# Connectors.net
KiCad netlist of a schematic drawn in Altium Designer
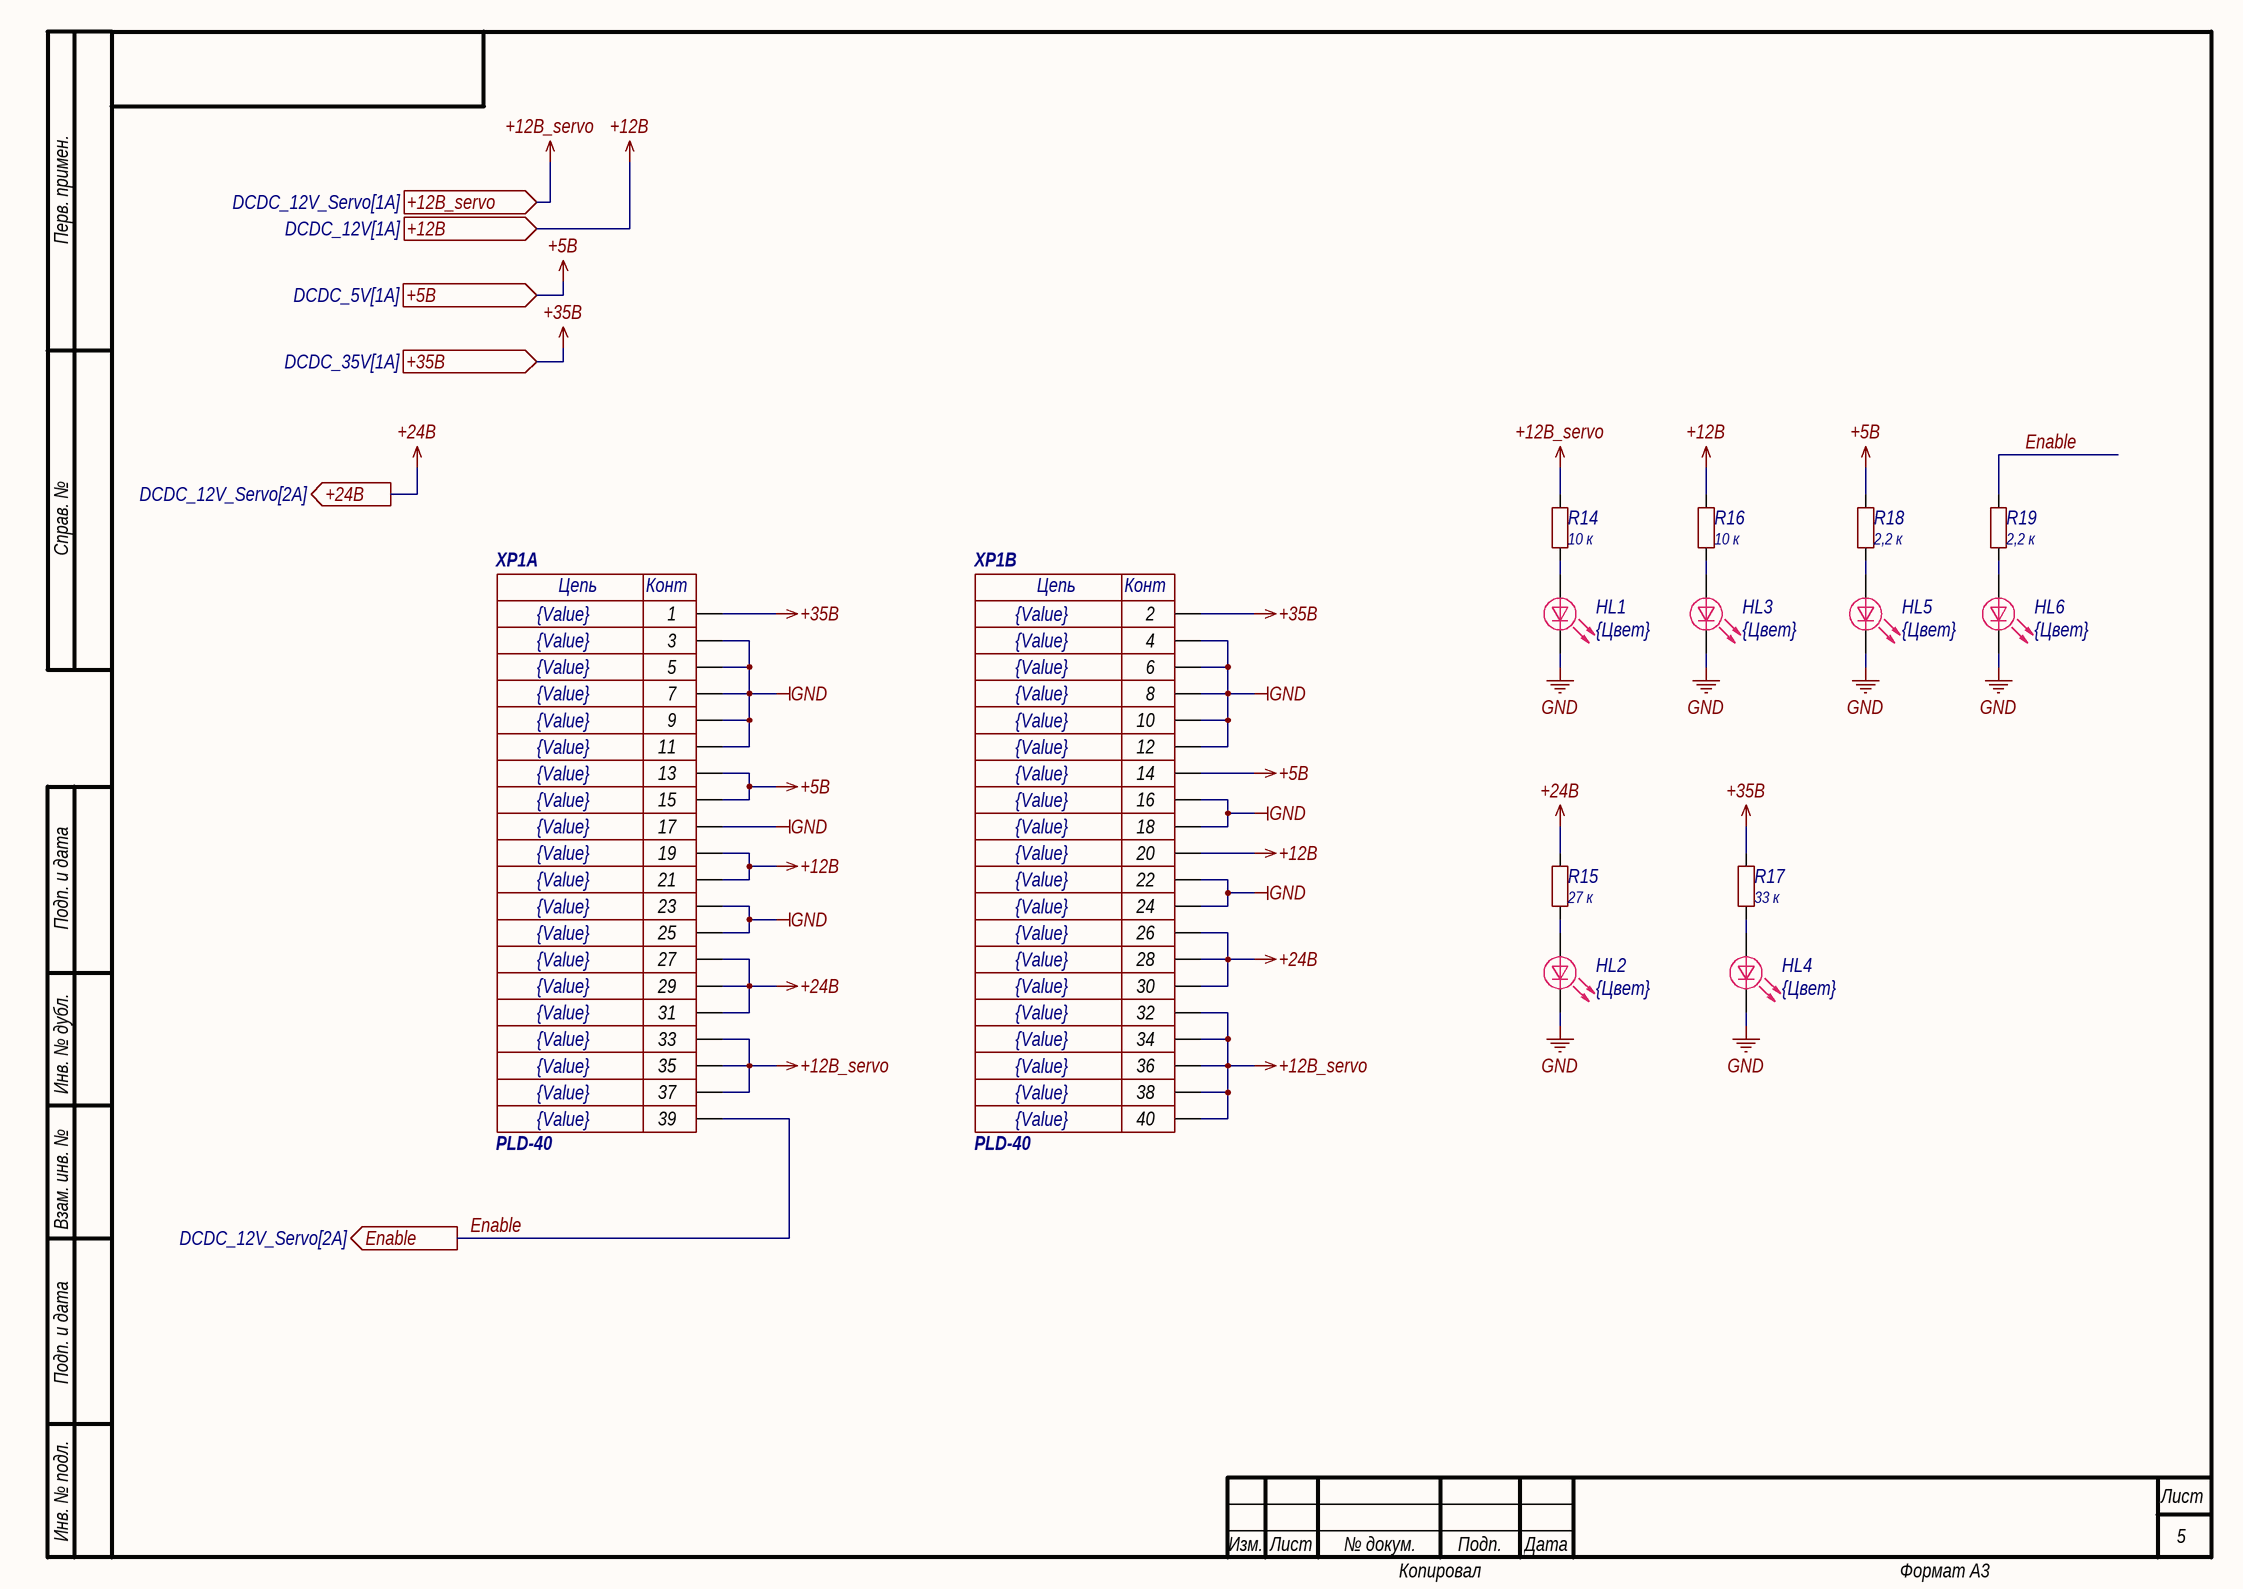
[diagram p0: Connectors.SchDoc]

(export (version "E")
  (design (tool "Eeschema 10.0.6"))
  (components
    (comp (ref "HL1")
      (value "LED")
      (footprint "0805D")
      (description "Светодиод")
      (fields (field (name "COLOR") "{Цвет}"))
      (libsource (lib "Hydrolib") (part "LED"))
    )
    (comp (ref "HL2")
      (value "LED")
      (footprint "0805D")
      (description "Светодиод")
      (fields (field (name "COLOR") "{Цвет}"))
      (libsource (lib "Hydrolib") (part "LED"))
    )
    (comp (ref "HL3")
      (value "LED")
      (footprint "0805D")
      (description "Светодиод")
      (fields (field (name "COLOR") "{Цвет}"))
      (libsource (lib "Hydrolib") (part "LED"))
    )
    (comp (ref "HL4")
      (value "LED")
      (footprint "0805D")
      (description "Светодиод")
      (fields (field (name "COLOR") "{Цвет}"))
      (libsource (lib "Hydrolib") (part "LED"))
    )
    (comp (ref "HL5")
      (value "LED")
      (footprint "0805D")
      (description "Светодиод")
      (fields (field (name "COLOR") "{Цвет}"))
      (libsource (lib "Hydrolib") (part "LED"))
    )
    (comp (ref "HL6")
      (value "LED")
      (footprint "0805D")
      (description "Светодиод")
      (fields (field (name "COLOR") "{Цвет}"))
      (libsource (lib "Hydrolib") (part "LED"))
    )
    (comp (ref "R14")
      (value "10 к")
      (footprint "0603R")
      (description "Резистор номиналом 10 кОм и точностью 1%")
      (fields (field (name "PART NUMBER") "Resistor_10k_1_0603") (field (name "TOLERANCE") "1%"))
      (libsource (lib "Hydrolib") (part "Resistor"))
    )
    (comp (ref "R15")
      (value "27 к")
      (footprint "0603R")
      (description "Резистор номиналом 27 кОм и точностью 1%")
      (fields (field (name "PART NUMBER") "Resistor_27k_1_0603") (field (name "TOLERANCE") "1%"))
      (libsource (lib "Hydrolib") (part "Resistor"))
    )
    (comp (ref "R16")
      (value "10 к")
      (footprint "0603R")
      (description "Резистор номиналом 10 кОм и точностью 1%")
      (fields (field (name "PART NUMBER") "Resistor_10k_1_0603") (field (name "TOLERANCE") "1%"))
      (libsource (lib "Hydrolib") (part "Resistor"))
    )
    (comp (ref "R17")
      (value "33 к")
      (footprint "0603R")
      (description "Резистор номиналом 33 кОм и точностью 1%")
      (fields (field (name "PART NUMBER") "Resistor_33k_1_0603") (field (name "TOLERANCE") "1%"))
      (libsource (lib "Hydrolib") (part "Resistor"))
    )
    (comp (ref "R18")
      (value "2,2 к")
      (footprint "0603R")
      (description "Резистор номиналом 2,2 кОм и точностью 1%")
      (fields (field (name "PART NUMBER") "Resistor_2.2k_1_0603") (field (name "TOLERANCE") "1%"))
      (libsource (lib "Hydrolib") (part "Resistor"))
    )
    (comp (ref "R19")
      (value "2,2 к")
      (footprint "0603R")
      (description "Резистор номиналом 2,2 кОм и точностью 1%")
      (fields (field (name "PART NUMBER") "Resistor_2.2k_1_0603") (field (name "TOLERANCE") "1%"))
      (libsource (lib "Hydrolib") (part "Resistor"))
    )
    (comp (ref "XP1")
      (value "PLD-40")
      (footprint "PLD40")
      (description "Гребенка 40 пинов")
      (fields
        (field (name "VALUE17") "{Value}")
        (field (name "VALUE20") "{Value}")
        (field (name "VALUE19") "{Value}")
        (field (name "VALUE18") "{Value}")
        (field (name "VALUE16") "{Value}")
        (field (name "VALUE15") "{Value}")
        (field (name "VALUE14") "{Value}")
        (field (name "VALUE13") "{Value}")
        (field (name "VALUE12") "{Value}")
        (field (name "VALUE11") "{Value}")
        (field (name "VALUE10") "{Value}")
        (field (name "VALUE9") "{Value}")
        (field (name "VALUE8") "{Value}")
        (field (name "VALUE7") "{Value}")
        (field (name "VALUE6") "{Value}")
        (field (name "VALUE5") "{Value}")
        (field (name "VALUE4") "{Value}")
        (field (name "VALUE3") "{Value}")
        (field (name "VALUE2") "{Value}")
        (field (name "VALUE1") "{Value}")
      )
      (libsource (lib "Hydrolib") (part "Conn_40pin_double"))
    )
  )
  (nets
    (net (code "1") (name "+5В") (class "Default")
      (node (ref "R18") (pin "2") (pinfunction "2_2") (pintype "passive"))
      (node (ref "XP1") (pin "13") (pinfunction "13_13") (pintype "passive"))
      (node (ref "XP1") (pin "14") (pinfunction "14_14") (pintype "passive"))
      (node (ref "XP1") (pin "15") (pinfunction "15_15") (pintype "passive"))
    )
    (net (code "2") (name "+12В") (class "Default")
      (node (ref "R16") (pin "2") (pinfunction "2_2") (pintype "passive"))
      (node (ref "XP1") (pin "19") (pinfunction "19_19") (pintype "passive"))
      (node (ref "XP1") (pin "20") (pinfunction "20_20") (pintype "passive"))
      (node (ref "XP1") (pin "21") (pinfunction "21_21") (pintype "passive"))
    )
    (net (code "3") (name "+12В_servo") (class "Default")
      (node (ref "R14") (pin "2") (pinfunction "2_2") (pintype "passive"))
      (node (ref "XP1") (pin "32") (pinfunction "32_32") (pintype "passive"))
      (node (ref "XP1") (pin "33") (pinfunction "33_33") (pintype "passive"))
      (node (ref "XP1") (pin "34") (pinfunction "34_34") (pintype "passive"))
      (node (ref "XP1") (pin "35") (pinfunction "35_35") (pintype "passive"))
      (node (ref "XP1") (pin "36") (pinfunction "36_36") (pintype "passive"))
      (node (ref "XP1") (pin "37") (pinfunction "37_37") (pintype "passive"))
      (node (ref "XP1") (pin "38") (pinfunction "38_38") (pintype "passive"))
      (node (ref "XP1") (pin "40") (pinfunction "40_40") (pintype "passive"))
    )
    (net (code "4") (name "+24В") (class "Default")
      (node (ref "R15") (pin "2") (pinfunction "2_2") (pintype "passive"))
      (node (ref "XP1") (pin "26") (pinfunction "26_26") (pintype "passive"))
      (node (ref "XP1") (pin "27") (pinfunction "27_27") (pintype "passive"))
      (node (ref "XP1") (pin "28") (pinfunction "28_28") (pintype "passive"))
      (node (ref "XP1") (pin "29") (pinfunction "29_29") (pintype "passive"))
      (node (ref "XP1") (pin "30") (pinfunction "30_30") (pintype "passive"))
      (node (ref "XP1") (pin "31") (pinfunction "31_31") (pintype "passive"))
    )
    (net (code "5") (name "+35В") (class "Default")
      (node (ref "R17") (pin "2") (pinfunction "2_2") (pintype "passive"))
      (node (ref "XP1") (pin "1") (pinfunction "1_1") (pintype "passive"))
      (node (ref "XP1") (pin "2") (pinfunction "2_2") (pintype "passive"))
    )
    (net (code "6") (name "/Enable") (class "Default")
      (node (ref "R19") (pin "2") (pinfunction "2_2") (pintype "passive"))
      (node (ref "XP1") (pin "39") (pinfunction "39_39") (pintype "passive"))
    )
    (net (code "7") (name "GND") (class "Default")
      (node (ref "HL1") (pin "2") (pinfunction "2_2") (pintype "passive"))
      (node (ref "HL2") (pin "2") (pinfunction "2_2") (pintype "passive"))
      (node (ref "HL3") (pin "2") (pinfunction "2_2") (pintype "passive"))
      (node (ref "HL4") (pin "2") (pinfunction "2_2") (pintype "passive"))
      (node (ref "HL5") (pin "2") (pinfunction "2_2") (pintype "passive"))
      (node (ref "HL6") (pin "2") (pinfunction "2_2") (pintype "passive"))
      (node (ref "XP1") (pin "10") (pinfunction "10_10") (pintype "passive"))
      (node (ref "XP1") (pin "11") (pinfunction "11_11") (pintype "passive"))
      (node (ref "XP1") (pin "12") (pinfunction "12_12") (pintype "passive"))
      (node (ref "XP1") (pin "16") (pinfunction "16_16") (pintype "passive"))
      (node (ref "XP1") (pin "17") (pinfunction "17_17") (pintype "passive"))
      (node (ref "XP1") (pin "18") (pinfunction "18_18") (pintype "passive"))
      (node (ref "XP1") (pin "22") (pinfunction "22_22") (pintype "passive"))
      (node (ref "XP1") (pin "23") (pinfunction "23_23") (pintype "passive"))
      (node (ref "XP1") (pin "24") (pinfunction "24_24") (pintype "passive"))
      (node (ref "XP1") (pin "25") (pinfunction "25_25") (pintype "passive"))
      (node (ref "XP1") (pin "3") (pinfunction "3_3") (pintype "passive"))
      (node (ref "XP1") (pin "4") (pinfunction "4_4") (pintype "passive"))
      (node (ref "XP1") (pin "5") (pinfunction "5_5") (pintype "passive"))
      (node (ref "XP1") (pin "6") (pinfunction "6_6") (pintype "passive"))
      (node (ref "XP1") (pin "7") (pinfunction "7_7") (pintype "passive"))
      (node (ref "XP1") (pin "8") (pinfunction "8_8") (pintype "passive"))
      (node (ref "XP1") (pin "9") (pinfunction "9_9") (pintype "passive"))
    )
    (net (code "8") (name "Net-(HL1-Pad1)") (class "Default")
      (node (ref "HL1") (pin "1") (pinfunction "1_1") (pintype "passive"))
      (node (ref "R14") (pin "1") (pinfunction "1_1") (pintype "passive"))
    )
    (net (code "9") (name "Net-(HL2-Pad1)") (class "Default")
      (node (ref "HL2") (pin "1") (pinfunction "1_1") (pintype "passive"))
      (node (ref "R15") (pin "1") (pinfunction "1_1") (pintype "passive"))
    )
    (net (code "10") (name "Net-(HL3-Pad1)") (class "Default")
      (node (ref "HL3") (pin "1") (pinfunction "1_1") (pintype "passive"))
      (node (ref "R16") (pin "1") (pinfunction "1_1") (pintype "passive"))
    )
    (net (code "11") (name "Net-(HL4-Pad1)") (class "Default")
      (node (ref "HL4") (pin "1") (pinfunction "1_1") (pintype "passive"))
      (node (ref "R17") (pin "1") (pinfunction "1_1") (pintype "passive"))
    )
    (net (code "12") (name "Net-(HL5-Pad1)") (class "Default")
      (node (ref "HL5") (pin "1") (pinfunction "1_1") (pintype "passive"))
      (node (ref "R18") (pin "1") (pinfunction "1_1") (pintype "passive"))
    )
    (net (code "13") (name "Net-(HL6-Pad1)") (class "Default")
      (node (ref "HL6") (pin "1") (pinfunction "1_1") (pintype "passive"))
      (node (ref "R19") (pin "1") (pinfunction "1_1") (pintype "passive"))
    )
  )
)
